# STLink_V3E_PWR.net
KiCad netlist of a schematic drawn in Altium Designer
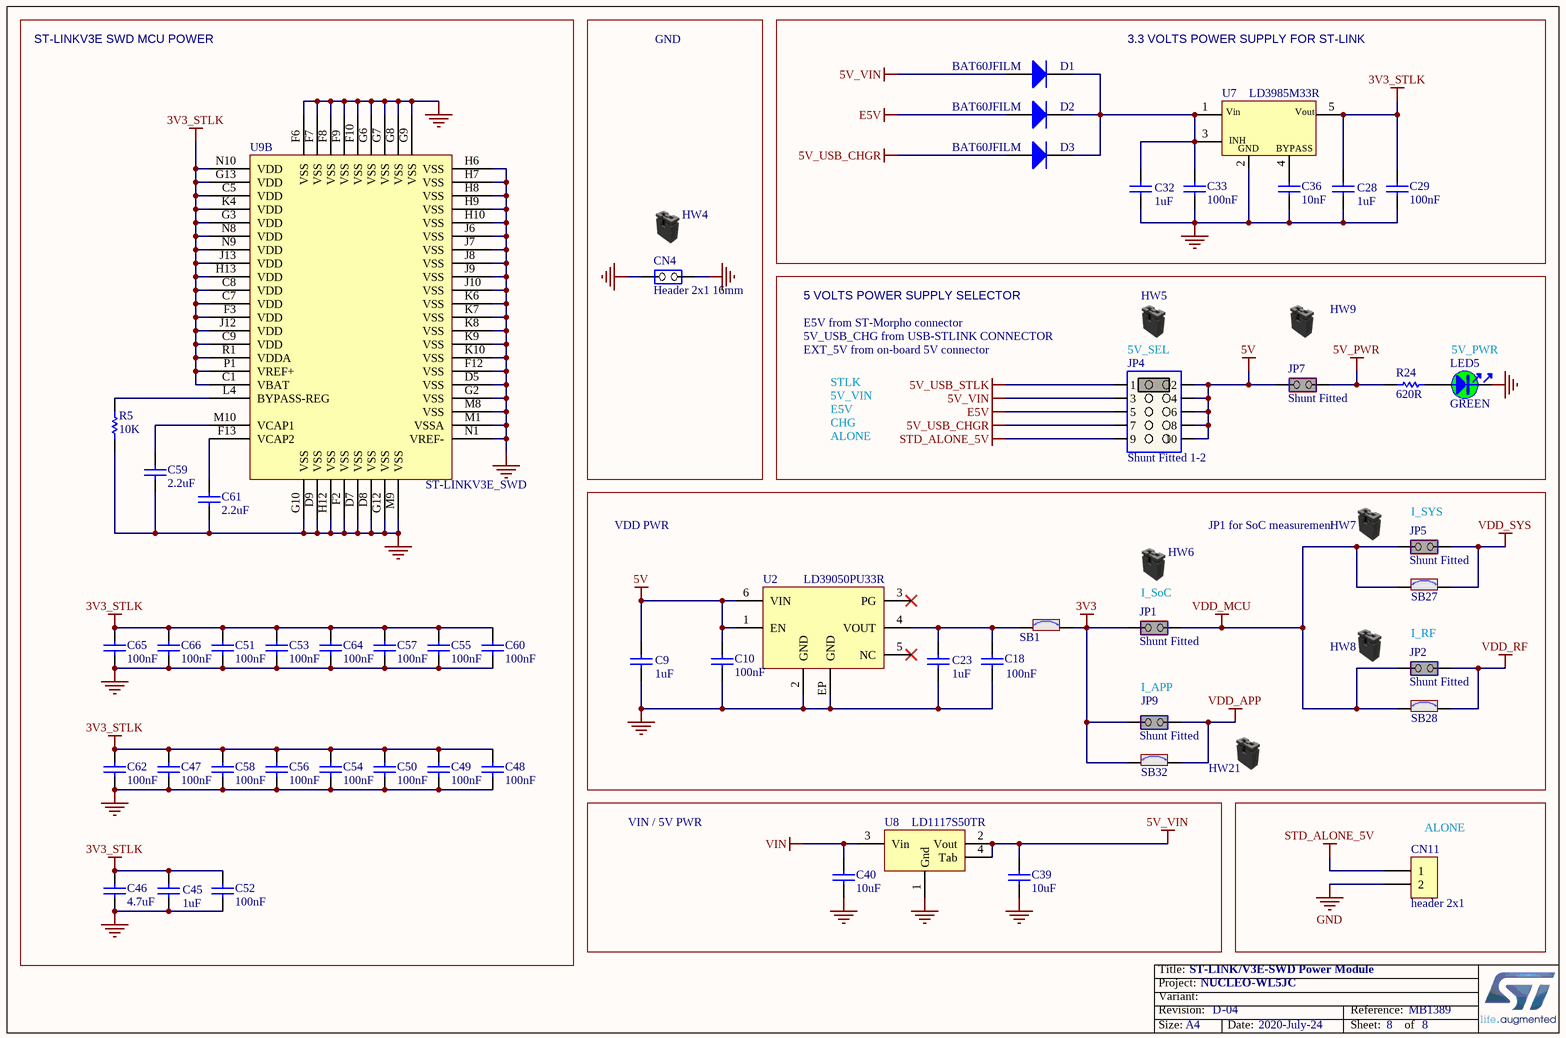
[diagram p0: STLink_V3E_PWR.SchDoc]

(export (version "E")
  (design (tool "Eeschema 10.0.6"))
  (components
    (comp (ref "C9")
      (value "1uF")
      (footprint "C0603")
      (description "Capacitor, MLCC, 1uF, 16V, X5R, 10%, 0603, T=0,8mm")
      (fields
        (field (name "INTERNAL_PART_NUMBER") "MCD-00010")
        (field (name "MANUFACTURER_PART_NUMBER") "CC0603KRX5R7BB105")
        (field (name "PROVIDED_BY") "SUBCO")
      )
      (libsource (lib "MCD_PARTS_database") (part "Capacitor"))
    )
    (comp (ref "C10")
      (value "100nF")
      (footprint "C0402")
      (description "Capacitor, MLCC, 100nF, 16V, X7R, 10%, 0402, T=0,5mm")
      (fields
        (field (name "INTERNAL_PART_NUMBER") "MCD-00102")
        (field (name "MANUFACTURER_PART_NUMBER") "CC0402KRX7R7BB104")
        (field (name "PROVIDED_BY") "SUBCO")
      )
      (libsource (lib "MCD_PARTS_database") (part "Capacitor"))
    )
    (comp (ref "C18")
      (value "100nF")
      (footprint "C0402")
      (description "Capacitor, MLCC, 100nF, 16V, X7R, 10%, 0402, T=0,5mm")
      (fields
        (field (name "INTERNAL_PART_NUMBER") "MCD-00102")
        (field (name "MANUFACTURER_PART_NUMBER") "CC0402KRX7R7BB104")
        (field (name "PROVIDED_BY") "SUBCO")
      )
      (libsource (lib "MCD_PARTS_database") (part "Capacitor"))
    )
    (comp (ref "C23")
      (value "1uF")
      (footprint "C0603")
      (description "Capacitor, MLCC, 1uF, 16V, X5R, 10%, 0603, T=0,8mm")
      (fields
        (field (name "INTERNAL_PART_NUMBER") "MCD-00010")
        (field (name "MANUFACTURER_PART_NUMBER") "CC0603KRX5R7BB105")
        (field (name "PROVIDED_BY") "SUBCO")
      )
      (libsource (lib "MCD_PARTS_database") (part "Capacitor"))
    )
    (comp (ref "C28")
      (value "1uF")
      (footprint "C0603")
      (description "Capacitor, MLCC, 1uF, 16V, X5R, 10%, 0603, T=0,8mm")
      (fields
        (field (name "INTERNAL_PART_NUMBER") "MCD-00010")
        (field (name "MANUFACTURER_PART_NUMBER") "CC0603KRX5R7BB105")
        (field (name "PROVIDED_BY") "SUBCO")
      )
      (libsource (lib "MCD_PARTS_database") (part "Capacitor"))
    )
    (comp (ref "C29")
      (value "100nF")
      (footprint "C0402")
      (description "Capacitor, MLCC, 100nF, 16V, X7R, 10%, 0402, T=0,5mm")
      (fields
        (field (name "INTERNAL_PART_NUMBER") "MCD-00102")
        (field (name "MANUFACTURER_PART_NUMBER") "CC0402KRX7R7BB104")
        (field (name "PROVIDED_BY") "SUBCO")
      )
      (libsource (lib "MCD_PARTS_database") (part "Capacitor"))
    )
    (comp (ref "C32")
      (value "1uF")
      (footprint "C0603")
      (description "Capacitor, MLCC, 1uF, 16V, X5R, 10%, 0603, T=0,8mm")
      (fields
        (field (name "INTERNAL_PART_NUMBER") "MCD-00010")
        (field (name "MANUFACTURER_PART_NUMBER") "CC0603KRX5R7BB105")
        (field (name "PROVIDED_BY") "SUBCO")
      )
      (libsource (lib "MCD_PARTS_database") (part "Capacitor"))
    )
    (comp (ref "C33")
      (value "100nF")
      (footprint "C0402")
      (description "Capacitor, MLCC, 100nF, 16V, X7R, 10%, 0402, T=0,5mm")
      (fields
        (field (name "INTERNAL_PART_NUMBER") "MCD-00102")
        (field (name "MANUFACTURER_PART_NUMBER") "CC0402KRX7R7BB104")
        (field (name "PROVIDED_BY") "SUBCO")
      )
      (libsource (lib "MCD_PARTS_database") (part "Capacitor"))
    )
    (comp (ref "C36")
      (value "10nF")
      (footprint "C0402")
      (description "Capacitor, MLCC, 10nF, 16V, X7R, 10%, 0402, T=0.5mm")
      (fields
        (field (name "INTERNAL_PART_NUMBER") "MCD-00011")
        (field (name "MANUFACTURER_PART_NUMBER") "CC0402KRX7R7BB103")
        (field (name "PROVIDED_BY") "SUBCO")
      )
      (libsource (lib "MCD_PARTS_database") (part "Capacitor"))
    )
    (comp (ref "C39")
      (value "10uF")
      (footprint "C0805")
      (description "Capacitor, MLCC, 10uF, 25V, X5R, 10%, 0805, T=0,85mm")
      (fields
        (field (name "INTERNAL_PART_NUMBER") "MCD-00014")
        (field (name "MANUFACTURER_PART_NUMBER") "CC0805KRX5R8BB106")
        (field (name "PROVIDED_BY") "SUBCO")
      )
      (libsource (lib "MCD_PARTS_database") (part "Capacitor"))
    )
    (comp (ref "C40")
      (value "10uF")
      (footprint "C0805")
      (description "Capacitor, MLCC, 10uF, 25V, X5R, 10%, 0805, T=0,85mm")
      (fields
        (field (name "INTERNAL_PART_NUMBER") "MCD-00014")
        (field (name "MANUFACTURER_PART_NUMBER") "CC0805KRX5R8BB106")
        (field (name "PROVIDED_BY") "SUBCO")
      )
      (libsource (lib "MCD_PARTS_database") (part "Capacitor"))
    )
    (comp (ref "C45")
      (value "1uF")
      (footprint "C0603")
      (description "Capacitor, MLCC, 1uF, 16V, X5R, 10%, 0603, T=0,8mm")
      (fields
        (field (name "INTERNAL_PART_NUMBER") "MCD-00010")
        (field (name "MANUFACTURER_PART_NUMBER") "CC0603KRX5R7BB105")
        (field (name "PROVIDED_BY") "SUBCO")
      )
      (libsource (lib "MCD_PARTS_database") (part "Capacitor"))
    )
    (comp (ref "C46")
      (value "4.7uF")
      (footprint "C0603")
      (description "Capacitor, MLCC, 4.7uF, 16V, X5R, 10%, 0603, T=0.8mm")
      (fields
        (field (name "INTERNAL_PART_NUMBER") "MCD-00009")
        (field (name "MANUFACTURER_PART_NUMBER") "CC0603KRX5R7BB475")
        (field (name "PROVIDED_BY") "SUBCO")
      )
      (libsource (lib "MCD_PARTS_database") (part "Capacitor"))
    )
    (comp (ref "C47")
      (value "100nF")
      (footprint "C0402")
      (description "Capacitor, MLCC, 100nF, 16V, X7R, 10%, 0402, T=0,5mm")
      (fields
        (field (name "INTERNAL_PART_NUMBER") "MCD-00102")
        (field (name "MANUFACTURER_PART_NUMBER") "CC0402KRX7R7BB104")
        (field (name "PROVIDED_BY") "SUBCO")
      )
      (libsource (lib "MCD_PARTS_database") (part "Capacitor"))
    )
    (comp (ref "C48")
      (value "100nF")
      (footprint "C0402")
      (description "Capacitor, MLCC, 100nF, 16V, X7R, 10%, 0402, T=0,5mm")
      (fields
        (field (name "INTERNAL_PART_NUMBER") "MCD-00102")
        (field (name "MANUFACTURER_PART_NUMBER") "CC0402KRX7R7BB104")
        (field (name "PROVIDED_BY") "SUBCO")
      )
      (libsource (lib "MCD_PARTS_database") (part "Capacitor"))
    )
    (comp (ref "C49")
      (value "100nF")
      (footprint "C0402")
      (description "Capacitor, MLCC, 100nF, 16V, X7R, 10%, 0402, T=0,5mm")
      (fields
        (field (name "INTERNAL_PART_NUMBER") "MCD-00102")
        (field (name "MANUFACTURER_PART_NUMBER") "CC0402KRX7R7BB104")
        (field (name "PROVIDED_BY") "SUBCO")
      )
      (libsource (lib "MCD_PARTS_database") (part "Capacitor"))
    )
    (comp (ref "C50")
      (value "100nF")
      (footprint "C0402")
      (description "Capacitor, MLCC, 100nF, 16V, X7R, 10%, 0402, T=0,5mm")
      (fields
        (field (name "INTERNAL_PART_NUMBER") "MCD-00102")
        (field (name "MANUFACTURER_PART_NUMBER") "CC0402KRX7R7BB104")
        (field (name "PROVIDED_BY") "SUBCO")
      )
      (libsource (lib "MCD_PARTS_database") (part "Capacitor"))
    )
    (comp (ref "C51")
      (value "100nF")
      (footprint "C0402")
      (description "Capacitor, MLCC, 100nF, 16V, X7R, 10%, 0402, T=0,5mm")
      (fields
        (field (name "INTERNAL_PART_NUMBER") "MCD-00102")
        (field (name "MANUFACTURER_PART_NUMBER") "CC0402KRX7R7BB104")
        (field (name "PROVIDED_BY") "SUBCO")
      )
      (libsource (lib "MCD_PARTS_database") (part "Capacitor"))
    )
    (comp (ref "C52")
      (value "100nF")
      (footprint "C0402")
      (description "Capacitor, MLCC, 100nF, 16V, X7R, 10%, 0402, T=0,5mm")
      (fields
        (field (name "INTERNAL_PART_NUMBER") "MCD-00102")
        (field (name "MANUFACTURER_PART_NUMBER") "CC0402KRX7R7BB104")
        (field (name "PROVIDED_BY") "SUBCO")
      )
      (libsource (lib "MCD_PARTS_database") (part "Capacitor"))
    )
    (comp (ref "C53")
      (value "100nF")
      (footprint "C0402")
      (description "Capacitor, MLCC, 100nF, 16V, X7R, 10%, 0402, T=0,5mm")
      (fields
        (field (name "INTERNAL_PART_NUMBER") "MCD-00102")
        (field (name "MANUFACTURER_PART_NUMBER") "CC0402KRX7R7BB104")
        (field (name "PROVIDED_BY") "SUBCO")
      )
      (libsource (lib "MCD_PARTS_database") (part "Capacitor"))
    )
    (comp (ref "C54")
      (value "100nF")
      (footprint "C0402")
      (description "Capacitor, MLCC, 100nF, 16V, X7R, 10%, 0402, T=0,5mm")
      (fields
        (field (name "INTERNAL_PART_NUMBER") "MCD-00102")
        (field (name "MANUFACTURER_PART_NUMBER") "CC0402KRX7R7BB104")
        (field (name "PROVIDED_BY") "SUBCO")
      )
      (libsource (lib "MCD_PARTS_database") (part "Capacitor"))
    )
    (comp (ref "C55")
      (value "100nF")
      (footprint "C0402")
      (description "Capacitor, MLCC, 100nF, 16V, X7R, 10%, 0402, T=0,5mm")
      (fields
        (field (name "INTERNAL_PART_NUMBER") "MCD-00102")
        (field (name "MANUFACTURER_PART_NUMBER") "CC0402KRX7R7BB104")
        (field (name "PROVIDED_BY") "SUBCO")
      )
      (libsource (lib "MCD_PARTS_database") (part "Capacitor"))
    )
    (comp (ref "C56")
      (value "100nF")
      (footprint "C0402")
      (description "Capacitor, MLCC, 100nF, 16V, X7R, 10%, 0402, T=0,5mm")
      (fields
        (field (name "INTERNAL_PART_NUMBER") "MCD-00102")
        (field (name "MANUFACTURER_PART_NUMBER") "CC0402KRX7R7BB104")
        (field (name "PROVIDED_BY") "SUBCO")
      )
      (libsource (lib "MCD_PARTS_database") (part "Capacitor"))
    )
    (comp (ref "C57")
      (value "100nF")
      (footprint "C0402")
      (description "Capacitor, MLCC, 100nF, 16V, X7R, 10%, 0402, T=0,5mm")
      (fields
        (field (name "INTERNAL_PART_NUMBER") "MCD-00102")
        (field (name "MANUFACTURER_PART_NUMBER") "CC0402KRX7R7BB104")
        (field (name "PROVIDED_BY") "SUBCO")
      )
      (libsource (lib "MCD_PARTS_database") (part "Capacitor"))
    )
    (comp (ref "C58")
      (value "100nF")
      (footprint "C0402")
      (description "Capacitor, MLCC, 100nF, 16V, X7R, 10%, 0402, T=0,5mm")
      (fields
        (field (name "INTERNAL_PART_NUMBER") "MCD-00102")
        (field (name "MANUFACTURER_PART_NUMBER") "CC0402KRX7R7BB104")
        (field (name "PROVIDED_BY") "SUBCO")
      )
      (libsource (lib "MCD_PARTS_database") (part "Capacitor"))
    )
    (comp (ref "C59")
      (value "2.2uF")
      (footprint "C0603")
      (description "Capacitor, MLCC, 2.2uF, 10V, X5R, 10%, 0603, T=0,8mm")
      (fields
        (field (name "INTERNAL_PART_NUMBER") "MCD-00012")
        (field (name "MANUFACTURER_PART_NUMBER") "CC0603KRX5R6BB225")
        (field (name "PROVIDED_BY") "SUBCO")
      )
      (libsource (lib "MCD_PARTS_database") (part "Capacitor"))
    )
    (comp (ref "C60")
      (value "100nF")
      (footprint "C0402")
      (description "Capacitor, MLCC, 100nF, 16V, X7R, 10%, 0402, T=0,5mm")
      (fields
        (field (name "INTERNAL_PART_NUMBER") "MCD-00102")
        (field (name "MANUFACTURER_PART_NUMBER") "CC0402KRX7R7BB104")
        (field (name "PROVIDED_BY") "SUBCO")
      )
      (libsource (lib "MCD_PARTS_database") (part "Capacitor"))
    )
    (comp (ref "C61")
      (value "2.2uF")
      (footprint "C0603")
      (description "Capacitor, MLCC, 2.2uF, 10V, X5R, 10%, 0603, T=0,8mm")
      (fields
        (field (name "INTERNAL_PART_NUMBER") "MCD-00012")
        (field (name "MANUFACTURER_PART_NUMBER") "CC0603KRX5R6BB225")
        (field (name "PROVIDED_BY") "SUBCO")
      )
      (libsource (lib "MCD_PARTS_database") (part "Capacitor"))
    )
    (comp (ref "C62")
      (value "100nF")
      (footprint "C0402")
      (description "Capacitor, MLCC, 100nF, 16V, X7R, 10%, 0402, T=0,5mm")
      (fields
        (field (name "INTERNAL_PART_NUMBER") "MCD-00102")
        (field (name "MANUFACTURER_PART_NUMBER") "CC0402KRX7R7BB104")
        (field (name "PROVIDED_BY") "SUBCO")
      )
      (libsource (lib "MCD_PARTS_database") (part "Capacitor"))
    )
    (comp (ref "C64")
      (value "100nF")
      (footprint "C0402")
      (description "Capacitor, MLCC, 100nF, 16V, X7R, 10%, 0402, T=0,5mm")
      (fields
        (field (name "INTERNAL_PART_NUMBER") "MCD-00102")
        (field (name "MANUFACTURER_PART_NUMBER") "CC0402KRX7R7BB104")
        (field (name "PROVIDED_BY") "SUBCO")
      )
      (libsource (lib "MCD_PARTS_database") (part "Capacitor"))
    )
    (comp (ref "C65")
      (value "100nF")
      (footprint "C0402")
      (description "Capacitor, MLCC, 100nF, 16V, X7R, 10%, 0402, T=0,5mm")
      (fields
        (field (name "INTERNAL_PART_NUMBER") "MCD-00102")
        (field (name "MANUFACTURER_PART_NUMBER") "CC0402KRX7R7BB104")
        (field (name "PROVIDED_BY") "SUBCO")
      )
      (libsource (lib "MCD_PARTS_database") (part "Capacitor"))
    )
    (comp (ref "C66")
      (value "100nF")
      (footprint "C0402")
      (description "Capacitor, MLCC, 100nF, 16V, X7R, 10%, 0402, T=0,5mm")
      (fields
        (field (name "INTERNAL_PART_NUMBER") "MCD-00102")
        (field (name "MANUFACTURER_PART_NUMBER") "CC0402KRX7R7BB104")
        (field (name "PROVIDED_BY") "SUBCO")
      )
      (libsource (lib "MCD_PARTS_database") (part "Capacitor"))
    )
    (comp (ref "CN4")
      (value "Header 2x1 16mm")
      (footprint "CON_SAMTEC_TSW-102-09-X-S")
      (description "Header, 2x1, 2,54mm, VR, TH, Height 5.84mm/10.16mm")
      (fields
        (field (name "INTERNAL_PART_NUMBER") "MCD-00214")
        (field (name "MANUFACTURER_PART_NUMBER") "TSW-102-09-x-S")
        (field (name "PROVIDED_BY") "SUBCO")
      )
      (libsource (lib "MCD_PARTS_database") (part "Jumper_Header 2x1"))
    )
    (comp (ref "CN11")
      (value "header 2x1")
      (footprint "CON_988-JIUBABA_PHFS25-11-02-G0B115-T-1")
      (description "Header, 2x1, 2.54mm, VR, TH, Height 6mm/3mm")
      (fields
        (field (name "INTERNAL_PART_NUMBER") "MCD-00314")
        (field (name "MANUFACTURER_PART_NUMBER") "PHFS25-11-02-G0B115-T-1")
        (field (name "PROVIDED_BY") "SUBCO")
      )
      (libsource (lib "MCD_PARTS_database") (part "Header 2x1"))
    )
    (comp (ref "D1")
      (value "BAT60JFILM")
      (footprint "DIO_SOD323")
      (fields
        (field (name "INTERNAL_PART_NUMBER") "MCD-00034")
        (field (name "MANUFACTURER") "STMICROELECTRONICS")
        (field (name "BMS_PART_NUMBER") "9151097")
        (field (name "PROVIDED_BY") "SUBCO with ST control")
      )
      (libsource (lib "MCD_PARTS_database") (part "BAT60JFILM"))
    )
    (comp (ref "D2")
      (value "BAT60JFILM")
      (footprint "DIO_SOD323")
      (fields
        (field (name "INTERNAL_PART_NUMBER") "MCD-00034")
        (field (name "MANUFACTURER") "STMICROELECTRONICS")
        (field (name "BMS_PART_NUMBER") "9151097")
        (field (name "PROVIDED_BY") "SUBCO with ST control")
      )
      (libsource (lib "MCD_PARTS_database") (part "BAT60JFILM"))
    )
    (comp (ref "D3")
      (value "BAT60JFILM")
      (footprint "DIO_SOD323")
      (fields
        (field (name "INTERNAL_PART_NUMBER") "MCD-00034")
        (field (name "MANUFACTURER") "STMICROELECTRONICS")
        (field (name "BMS_PART_NUMBER") "9151097")
        (field (name "PROVIDED_BY") "SUBCO with ST control")
      )
      (libsource (lib "MCD_PARTS_database") (part "BAT60JFILM"))
    )
    (comp (ref "HW4")
      (value "~")
      (description "SHUNT 2.54mm BLACK")
      (fields
        (field (name "INTERNAL_PART_NUMBER") "MCD-00043")
        (field (name "MANUFACTURER_PART_NUMBER") "SNT-100-BK-G")
        (field (name "PROVIDED_BY") "SUBCO")
      )
      (libsource (lib "MCD_PARTS_database") (part "Shunt Black 2.54mm"))
    )
    (comp (ref "HW5")
      (value "~")
      (description "SHUNT 2.54mm BLACK")
      (fields
        (field (name "INTERNAL_PART_NUMBER") "MCD-00043")
        (field (name "MANUFACTURER_PART_NUMBER") "SNT-100-BK-G")
        (field (name "PROVIDED_BY") "SUBCO")
      )
      (libsource (lib "MCD_PARTS_database") (part "Shunt Black 2.54mm"))
    )
    (comp (ref "HW6")
      (value "~")
      (description "SHUNT 2.54mm BLACK")
      (fields
        (field (name "INTERNAL_PART_NUMBER") "MCD-00043")
        (field (name "MANUFACTURER_PART_NUMBER") "SNT-100-BK-G")
        (field (name "PROVIDED_BY") "SUBCO")
      )
      (libsource (lib "MCD_PARTS_database") (part "Shunt Black 2.54mm"))
    )
    (comp (ref "HW7")
      (value "~")
      (description "SHUNT 2.54mm BLACK")
      (fields
        (field (name "INTERNAL_PART_NUMBER") "MCD-00043")
        (field (name "MANUFACTURER_PART_NUMBER") "SNT-100-BK-G")
        (field (name "PROVIDED_BY") "SUBCO")
      )
      (libsource (lib "MCD_PARTS_database") (part "Shunt Black 2.54mm"))
    )
    (comp (ref "HW8")
      (value "~")
      (description "SHUNT 2.54mm BLACK")
      (fields
        (field (name "INTERNAL_PART_NUMBER") "MCD-00043")
        (field (name "MANUFACTURER_PART_NUMBER") "SNT-100-BK-G")
        (field (name "PROVIDED_BY") "SUBCO")
      )
      (libsource (lib "MCD_PARTS_database") (part "Shunt Black 2.54mm"))
    )
    (comp (ref "HW9")
      (value "~")
      (description "SHUNT 2.54mm BLACK")
      (fields
        (field (name "INTERNAL_PART_NUMBER") "MCD-00043")
        (field (name "MANUFACTURER_PART_NUMBER") "SNT-100-BK-G")
        (field (name "PROVIDED_BY") "SUBCO")
      )
      (libsource (lib "MCD_PARTS_database") (part "Shunt Black 2.54mm"))
    )
    (comp (ref "HW21")
      (value "~")
      (description "SHUNT 2.54mm BLACK")
      (fields
        (field (name "INTERNAL_PART_NUMBER") "MCD-00043")
        (field (name "MANUFACTURER_PART_NUMBER") "SNT-100-BK-G")
        (field (name "PROVIDED_BY") "SUBCO")
      )
      (libsource (lib "MCD_PARTS_database") (part "Shunt Black 2.54mm"))
    )
    (comp (ref "JP1")
      (value "Shunt Fitted")
      (footprint "CON_SAMTEC_TSW-102-07-G-S")
      (description "Header, 2x1, 2,54mm, VR, TH, Height 5.84mm/2.54mm - Shunt Fitted by default")
      (fields
        (field (name "INTERNAL_PART_NUMBER") "MCD-00683")
        (field (name "MANUFACTURER_PART_NUMBER") "TSW-102-07-x-S")
        (field (name "PROVIDED_BY") "SUBCO")
      )
      (libsource (lib "MCD_PARTS_database") (part "Jumper_Header 2x1 Fitted"))
    )
    (comp (ref "JP2")
      (value "Shunt Fitted")
      (footprint "CON_SAMTEC_TSW-102-07-G-S")
      (description "Header, 2x1, 2,54mm, VR, TH, Height 5.84mm/2.54mm - Shunt Fitted by default")
      (fields
        (field (name "INTERNAL_PART_NUMBER") "MCD-00683")
        (field (name "MANUFACTURER_PART_NUMBER") "TSW-102-07-x-S")
        (field (name "PROVIDED_BY") "SUBCO")
      )
      (libsource (lib "MCD_PARTS_database") (part "Jumper_Header 2x1 Fitted"))
    )
    (comp (ref "JP4")
      (value "Shunt Fitted 1-2")
      (footprint "CON_SAMTEC_TSW-105-07-X-D")
      (description "Header, 5x2, 2,54mm, VR, TH, Height 5.84mm/2.54mm - Shunt Fitted 1-2")
      (fields
        (field (name "INTERNAL_PART_NUMBER") "MCD-01203")
        (field (name "MANUFACTURER_PART_NUMBER") "TSW-105-07-x-D")
        (field (name "PROVIDED_BY") "SUBCO")
      )
      (libsource (lib "MCD_PARTS_database") (part "Jumper_Header 5x2 Fitted 1-2"))
    )
    (comp (ref "JP5")
      (value "Shunt Fitted")
      (footprint "CON_SAMTEC_TSW-102-07-G-S")
      (description "Header, 2x1, 2,54mm, VR, TH, Height 5.84mm/2.54mm - Shunt Fitted by default")
      (fields
        (field (name "INTERNAL_PART_NUMBER") "MCD-00683")
        (field (name "MANUFACTURER_PART_NUMBER") "TSW-102-07-x-S")
        (field (name "PROVIDED_BY") "SUBCO")
      )
      (libsource (lib "MCD_PARTS_database") (part "Jumper_Header 2x1 Fitted"))
    )
    (comp (ref "JP7")
      (value "Shunt Fitted")
      (footprint "CON_SAMTEC_TSW-102-07-G-S")
      (description "Header, 2x1, 2,54mm, VR, TH, Height 5.84mm/2.54mm - Shunt Fitted by default")
      (fields
        (field (name "INTERNAL_PART_NUMBER") "MCD-00683")
        (field (name "MANUFACTURER_PART_NUMBER") "TSW-102-07-x-S")
        (field (name "PROVIDED_BY") "SUBCO")
      )
      (libsource (lib "MCD_PARTS_database") (part "Jumper_Header 2x1 Fitted"))
    )
    (comp (ref "JP9")
      (value "Shunt Fitted")
      (footprint "CON_SAMTEC_TSW-102-07-G-S")
      (description "Header, 2x1, 2,54mm, VR, TH, Height 5.84mm/2.54mm - Shunt Fitted by default")
      (fields
        (field (name "INTERNAL_PART_NUMBER") "MCD-00683")
        (field (name "MANUFACTURER_PART_NUMBER") "TSW-102-07-x-S")
        (field (name "PROVIDED_BY") "SUBCO")
      )
      (libsource (lib "MCD_PARTS_database") (part "Jumper_Header 2x1 Fitted"))
    )
    (comp (ref "LED5")
      (value "GREEN")
      (footprint "LED_0603_OSRAM_LG-Q396-PS-35_GREEN_1A2K_H0P4")
      (description "LED Green, 0603 SMD, Forward Voltage Typ=2V, Max=2.5V")
      (fields
        (field (name "INTERNAL_PART_NUMBER") "MCD-00588")
        (field (name "MANUFACTURER_PART_NUMBER") "LG Q396-PS-35")
        (field (name "PROVIDED_BY") "SUBCO")
      )
      (libsource (lib "MCD_PARTS_database") (part "LED_green"))
    )
    (comp (ref "R5")
      (value "10K")
      (footprint "R0402")
      (description "Resistor,10K,0402,1%,1/16W")
      (fields
        (field (name "INTERNAL_PART_NUMBER") "MCD-00053")
        (field (name "MANUFACTURER_PART_NUMBER") "RC0402FR-0710KL")
        (field (name "PROVIDED_BY") "SUBCO")
      )
      (libsource (lib "MCD_PARTS_database") (part "Resistor"))
    )
    (comp (ref "R24")
      (value "620R")
      (footprint "R0402")
      (description "Resistor,620R,0402,1%,1/16W")
      (fields
        (field (name "INTERNAL_PART_NUMBER") "MCD-00499")
        (field (name "MANUFACTURER_PART_NUMBER") "RC0402FR-07620RL")
        (field (name "PROVIDED_BY") "SUBCO")
      )
      (libsource (lib "MCD_PARTS_database") (part "Resistor"))
    )
    (comp (ref "SB1")
      (value "~")
      (footprint "SOLDER-BRIDGE_R0603-0R")
      (description "Solder Bridge ON")
      (fields
        (field (name "INTERNAL_PART_NUMBER") "MCD-00071")
        (field (name "MANUFACTURER_PART_NUMBER") "RC0603JR-070RL")
        (field (name "PROVIDED_BY") "SUBCO")
      )
      (libsource (lib "MCD_PARTS_database") (part "SB_ON"))
    )
    (comp (ref "SB27")
      (value "~")
      (footprint "SOLDER-BRIDGE_R0603-0R")
      (description "Solder Bridge ON")
      (fields
        (field (name "INTERNAL_PART_NUMBER") "MCD-00071")
        (field (name "MANUFACTURER_PART_NUMBER") "RC0603JR-070RL")
        (field (name "PROVIDED_BY") "SUBCO")
      )
      (libsource (lib "MCD_PARTS_database") (part "SB_ON"))
    )
    (comp (ref "SB28")
      (value "~")
      (footprint "SOLDER-BRIDGE_R0603-0R")
      (description "Solder Bridge ON")
      (fields
        (field (name "INTERNAL_PART_NUMBER") "MCD-00071")
        (field (name "MANUFACTURER_PART_NUMBER") "RC0603JR-070RL")
        (field (name "PROVIDED_BY") "SUBCO")
      )
      (libsource (lib "MCD_PARTS_database") (part "SB_ON"))
    )
    (comp (ref "SB32")
      (value "~")
      (footprint "SOLDER-BRIDGE_R0603-0R")
      (description "Solder Bridge ON")
      (fields
        (field (name "INTERNAL_PART_NUMBER") "MCD-00071")
        (field (name "MANUFACTURER_PART_NUMBER") "RC0603JR-070RL")
        (field (name "PROVIDED_BY") "SUBCO")
      )
      (libsource (lib "MCD_PARTS_database") (part "SB_ON"))
    )
    (comp (ref "U2")
      (value "LD39050PU33R")
      (footprint "ICC_DFN6-EPAD_3X3_P095")
      (description "Low quiescent current and low noise voltage regulators")
      (fields
        (field (name "INTERNAL_PART_NUMBER") "MCD-00215")
        (field (name "MANUFACTURER") "STMICROELECTRONICS")
        (field (name "PROVIDED_BY") "SUBCO with ST control")
      )
      (libsource (lib "MCD_PARTS_database") (part "LD39050PU33R"))
    )
    (comp (ref "U7")
      (value "LD3985M33R")
      (footprint "REG_SOT23-5L")
      (description "Ultra low drop-low noise BiCMOS voltage, regulators low ESR capacitors compatible")
      (fields
        (field (name "INTERNAL_PART_NUMBER") "MCD-00086")
        (field (name "MANUFACTURER") "STMICROELECTRONICS")
        (field (name "PROVIDED_BY") "SUBCO with ST control")
      )
      (libsource (lib "MCD_PARTS_database") (part "LD3985M33R"))
    )
    (comp (ref "U8")
      (value "LD1117S50TR")
      (footprint "REG_SOT223-TAB")
      (description "IC REG LDO 5V 0.8A SOT223")
      (fields
        (field (name "INTERNAL_PART_NUMBER") "MCD-00088")
        (field (name "MANUFACTURER") "STMICROELECTRONICS")
        (field (name "PROVIDED_BY") "SUBCO with ST control")
      )
      (libsource (lib "MCD_PARTS_database") (part "LD1117S50TR"))
    )
    (comp (ref "U9")
      (value "ST-LINKV3E_SWD")
      (footprint "ICC_UFBGA201_176+25_10X10_P065")
      (description "STM32F723IEK  (STM32F7) BGA176")
      (fields
        (field (name "INTERNAL_PART_NUMBER") "MCD-00596")
        (field (name "MANUFACTURER_PART_NUMBER") "STM32F723IEK6")
        (field (name "PROVIDED_BY") "SUBCO with ST control")
      )
      (libsource (lib "MCD_PARTS_database") (part "ST-LINKV3E_SWD"))
    )
  )
  (nets
    (net (code "1") (name "3V3") (class "Default")
      (node (ref "JP1") (pin "1") (pinfunction "COMMON_1") (pintype "passive"))
      (node (ref "JP9") (pin "1") (pinfunction "COMMON_1") (pintype "passive"))
      (node (ref "SB1") (pin "2") (pinfunction "2_2") (pintype "passive"))
      (node (ref "SB32") (pin "1") (pinfunction "1_1") (pintype "passive"))
    )
    (net (code "2") (name "3V3_STLK") (class "Default")
      (node (ref "C28") (pin "2") (pinfunction "2_2") (pintype "passive"))
      (node (ref "C29") (pin "2") (pinfunction "2_2") (pintype "passive"))
      (node (ref "C45") (pin "2") (pinfunction "2_2") (pintype "passive"))
      (node (ref "C46") (pin "2") (pinfunction "2_2") (pintype "passive"))
      (node (ref "C47") (pin "2") (pinfunction "2_2") (pintype "passive"))
      (node (ref "C48") (pin "2") (pinfunction "2_2") (pintype "passive"))
      (node (ref "C49") (pin "2") (pinfunction "2_2") (pintype "passive"))
      (node (ref "C50") (pin "2") (pinfunction "2_2") (pintype "passive"))
      (node (ref "C51") (pin "2") (pinfunction "2_2") (pintype "passive"))
      (node (ref "C52") (pin "2") (pinfunction "2_2") (pintype "passive"))
      (node (ref "C53") (pin "2") (pinfunction "2_2") (pintype "passive"))
      (node (ref "C54") (pin "2") (pinfunction "2_2") (pintype "passive"))
      (node (ref "C55") (pin "2") (pinfunction "2_2") (pintype "passive"))
      (node (ref "C56") (pin "2") (pinfunction "2_2") (pintype "passive"))
      (node (ref "C57") (pin "2") (pinfunction "2_2") (pintype "passive"))
      (node (ref "C58") (pin "2") (pinfunction "2_2") (pintype "passive"))
      (node (ref "C60") (pin "2") (pinfunction "2_2") (pintype "passive"))
      (node (ref "C62") (pin "2") (pinfunction "2_2") (pintype "passive"))
      (node (ref "C64") (pin "2") (pinfunction "2_2") (pintype "passive"))
      (node (ref "C65") (pin "2") (pinfunction "2_2") (pintype "passive"))
      (node (ref "C66") (pin "2") (pinfunction "2_2") (pintype "passive"))
      (node (ref "U7") (pin "5") (pinfunction "Vout_5") (pintype "passive"))
      (node (ref "U9") (pin "C1") (pinfunction "VBAT_C1") (pintype "passive"))
      (node (ref "U9") (pin "C5") (pinfunction "VDD_C5") (pintype "passive"))
      (node (ref "U9") (pin "C7") (pinfunction "VDD_C7") (pintype "passive"))
      (node (ref "U9") (pin "C8") (pinfunction "VDD_C8") (pintype "passive"))
      (node (ref "U9") (pin "C9") (pinfunction "VDD_C9") (pintype "passive"))
      (node (ref "U9") (pin "F3") (pinfunction "VDD_F3") (pintype "passive"))
      (node (ref "U9") (pin "G13") (pinfunction "VDD_G13") (pintype "passive"))
      (node (ref "U9") (pin "G3") (pinfunction "VDD_G3") (pintype "passive"))
      (node (ref "U9") (pin "H13") (pinfunction "VDD_H13") (pintype "passive"))
      (node (ref "U9") (pin "J12") (pinfunction "VDD_J12") (pintype "passive"))
      (node (ref "U9") (pin "J13") (pinfunction "VDD_J13") (pintype "passive"))
      (node (ref "U9") (pin "K4") (pinfunction "VDD_K4") (pintype "passive"))
      (node (ref "U9") (pin "N10") (pinfunction "VDD_N10") (pintype "passive"))
      (node (ref "U9") (pin "N8") (pinfunction "VDD_N8") (pintype "passive"))
      (node (ref "U9") (pin "N9") (pinfunction "VDD_N9") (pintype "passive"))
      (node (ref "U9") (pin "P1") (pinfunction "VREF+_P1") (pintype "passive"))
      (node (ref "U9") (pin "R1") (pinfunction "VDDA_R1") (pintype "passive"))
    )
    (net (code "3") (name "5V") (class "Default")
      (node (ref "C10") (pin "2") (pinfunction "2_2") (pintype "passive"))
      (node (ref "C9") (pin "2") (pinfunction "2_2") (pintype "passive"))
      (node (ref "JP4") (pin "10") (pinfunction "10_10") (pintype "passive"))
      (node (ref "JP4") (pin "2") (pinfunction "2_2") (pintype "passive"))
      (node (ref "JP4") (pin "4") (pinfunction "4_4") (pintype "passive"))
      (node (ref "JP4") (pin "6") (pinfunction "6_6") (pintype "passive"))
      (node (ref "JP4") (pin "8") (pinfunction "8_8") (pintype "passive"))
      (node (ref "JP7") (pin "1") (pinfunction "COMMON_1") (pintype "passive"))
      (node (ref "U2") (pin "1") (pinfunction "EN_1") (pintype "passive"))
      (node (ref "U2") (pin "6") (pinfunction "VIN_6") (pintype "passive"))
    )
    (net (code "4") (name "5V_PWR") (class "Default")
      (node (ref "JP7") (pin "2") (pinfunction "NO_2") (pintype "passive"))
      (node (ref "R24") (pin "1") (pinfunction "1_1") (pintype "passive"))
    )
    (net (code "5") (name "5V_USB_CHGR") (class "Default")
      (node (ref "D3") (pin "1") (pinfunction "A_1") (pintype "passive"))
      (node (ref "JP4") (pin "7") (pinfunction "7_7") (pintype "passive"))
    )
    (net (code "6") (name "5V_USB_STLK") (class "Default")
      (node (ref "JP4") (pin "1") (pinfunction "1_1") (pintype "passive"))
    )
    (net (code "7") (name "5V_VIN") (class "Default")
      (node (ref "C39") (pin "2") (pinfunction "2_2") (pintype "passive"))
      (node (ref "D1") (pin "1") (pinfunction "A_1") (pintype "passive"))
      (node (ref "JP4") (pin "3") (pinfunction "3_3") (pintype "passive"))
      (node (ref "U8") (pin "2") (pinfunction "Vout_2") (pintype "passive"))
      (node (ref "U8") (pin "4") (pinfunction "Tab_4") (pintype "passive"))
    )
    (net (code "8") (name "E5V") (class "Default")
      (node (ref "D2") (pin "1") (pinfunction "A_1") (pintype "passive"))
      (node (ref "JP4") (pin "5") (pinfunction "5_5") (pintype "passive"))
    )
    (net (code "9") (name "GND") (class "Default")
      (node (ref "C10") (pin "1") (pinfunction "1_1") (pintype "passive"))
      (node (ref "C18") (pin "1") (pinfunction "1_1") (pintype "passive"))
      (node (ref "C23") (pin "1") (pinfunction "1_1") (pintype "passive"))
      (node (ref "C28") (pin "1") (pinfunction "1_1") (pintype "passive"))
      (node (ref "C29") (pin "1") (pinfunction "1_1") (pintype "passive"))
      (node (ref "C32") (pin "1") (pinfunction "1_1") (pintype "passive"))
      (node (ref "C33") (pin "1") (pinfunction "1_1") (pintype "passive"))
      (node (ref "C36") (pin "1") (pinfunction "1_1") (pintype "passive"))
      (node (ref "C39") (pin "1") (pinfunction "1_1") (pintype "passive"))
      (node (ref "C40") (pin "1") (pinfunction "1_1") (pintype "passive"))
      (node (ref "C45") (pin "1") (pinfunction "1_1") (pintype "passive"))
      (node (ref "C46") (pin "1") (pinfunction "1_1") (pintype "passive"))
      (node (ref "C47") (pin "1") (pinfunction "1_1") (pintype "passive"))
      (node (ref "C48") (pin "1") (pinfunction "1_1") (pintype "passive"))
      (node (ref "C49") (pin "1") (pinfunction "1_1") (pintype "passive"))
      (node (ref "C50") (pin "1") (pinfunction "1_1") (pintype "passive"))
      (node (ref "C51") (pin "1") (pinfunction "1_1") (pintype "passive"))
      (node (ref "C52") (pin "1") (pinfunction "1_1") (pintype "passive"))
      (node (ref "C53") (pin "1") (pinfunction "1_1") (pintype "passive"))
      (node (ref "C54") (pin "1") (pinfunction "1_1") (pintype "passive"))
      (node (ref "C55") (pin "1") (pinfunction "1_1") (pintype "passive"))
      (node (ref "C56") (pin "1") (pinfunction "1_1") (pintype "passive"))
      (node (ref "C57") (pin "1") (pinfunction "1_1") (pintype "passive"))
      (node (ref "C58") (pin "1") (pinfunction "1_1") (pintype "passive"))
      (node (ref "C59") (pin "1") (pinfunction "1_1") (pintype "passive"))
      (node (ref "C60") (pin "1") (pinfunction "1_1") (pintype "passive"))
      (node (ref "C61") (pin "1") (pinfunction "1_1") (pintype "passive"))
      (node (ref "C62") (pin "1") (pinfunction "1_1") (pintype "passive"))
      (node (ref "C64") (pin "1") (pinfunction "1_1") (pintype "passive"))
      (node (ref "C65") (pin "1") (pinfunction "1_1") (pintype "passive"))
      (node (ref "C66") (pin "1") (pinfunction "1_1") (pintype "passive"))
      (node (ref "C9") (pin "1") (pinfunction "1_1") (pintype "passive"))
      (node (ref "CN11") (pin "2") (pinfunction "2_2") (pintype "passive"))
      (node (ref "CN4") (pin "1") (pinfunction "COMMON_1") (pintype "passive"))
      (node (ref "CN4") (pin "2") (pinfunction "NO_2") (pintype "passive"))
      (node (ref "LED5") (pin "2") (pintype "passive"))
      (node (ref "R5") (pin "1") (pinfunction "1_1") (pintype "passive"))
      (node (ref "U2") (pin "2") (pinfunction "GND_2") (pintype "passive"))
      (node (ref "U2") (pin "EP") (pinfunction "GND_EP") (pintype "passive"))
      (node (ref "U7") (pin "2") (pinfunction "GND_2") (pintype "passive"))
      (node (ref "U8") (pin "1") (pinfunction "Gnd_1") (pintype "passive"))
      (node (ref "U9") (pin "D5") (pinfunction "VSS_D5") (pintype "passive"))
      (node (ref "U9") (pin "D7") (pinfunction "VSS_D7") (pintype "passive"))
      (node (ref "U9") (pin "D8") (pinfunction "VSS_D8") (pintype "passive"))
      (node (ref "U9") (pin "D9") (pinfunction "VSS_D9") (pintype "passive"))
      (node (ref "U9") (pin "F10") (pinfunction "VSS_F10") (pintype "passive"))
      (node (ref "U9") (pin "F12") (pinfunction "VSS_F12") (pintype "passive"))
      (node (ref "U9") (pin "F2") (pinfunction "VSS_F2") (pintype "passive"))
      (node (ref "U9") (pin "F6") (pinfunction "VSS_F6") (pintype "passive"))
      (node (ref "U9") (pin "F7") (pinfunction "VSS_F7") (pintype "passive"))
      (node (ref "U9") (pin "F8") (pinfunction "VSS_F8") (pintype "passive"))
      (node (ref "U9") (pin "F9") (pinfunction "VSS_F9") (pintype "passive"))
      (node (ref "U9") (pin "G10") (pinfunction "VSS_G10") (pintype "passive"))
      (node (ref "U9") (pin "G12") (pinfunction "VSS_G12") (pintype "passive"))
      (node (ref "U9") (pin "G2") (pinfunction "VSS_G2") (pintype "passive"))
      (node (ref "U9") (pin "G6") (pinfunction "VSS_G6") (pintype "passive"))
      (node (ref "U9") (pin "G7") (pinfunction "VSS_G7") (pintype "passive"))
      (node (ref "U9") (pin "G8") (pinfunction "VSS_G8") (pintype "passive"))
      (node (ref "U9") (pin "G9") (pinfunction "VSS_G9") (pintype "passive"))
      (node (ref "U9") (pin "H10") (pinfunction "VSS_H10") (pintype "passive"))
      (node (ref "U9") (pin "H12") (pinfunction "VSS_H12") (pintype "passive"))
      (node (ref "U9") (pin "H6") (pinfunction "VSS_H6") (pintype "passive"))
      (node (ref "U9") (pin "H7") (pinfunction "VSS_H7") (pintype "passive"))
      (node (ref "U9") (pin "H8") (pinfunction "VSS_H8") (pintype "passive"))
      (node (ref "U9") (pin "H9") (pinfunction "VSS_H9") (pintype "passive"))
      (node (ref "U9") (pin "J10") (pinfunction "VSS_J10") (pintype "passive"))
      (node (ref "U9") (pin "J6") (pinfunction "VSS_J6") (pintype "passive"))
      (node (ref "U9") (pin "J7") (pinfunction "VSS_J7") (pintype "passive"))
      (node (ref "U9") (pin "J8") (pinfunction "VSS_J8") (pintype "passive"))
      (node (ref "U9") (pin "J9") (pinfunction "VSS_J9") (pintype "passive"))
      (node (ref "U9") (pin "K10") (pinfunction "VSS_K10") (pintype "passive"))
      (node (ref "U9") (pin "K6") (pinfunction "VSS_K6") (pintype "passive"))
      (node (ref "U9") (pin "K7") (pinfunction "VSS_K7") (pintype "passive"))
      (node (ref "U9") (pin "K8") (pinfunction "VSS_K8") (pintype "passive"))
      (node (ref "U9") (pin "K9") (pinfunction "VSS_K9") (pintype "passive"))
      (node (ref "U9") (pin "M1") (pinfunction "VSSA_M1") (pintype "passive"))
      (node (ref "U9") (pin "M8") (pinfunction "VSS_M8") (pintype "passive"))
      (node (ref "U9") (pin "M9") (pinfunction "VSS_M9") (pintype "passive"))
      (node (ref "U9") (pin "N1") (pinfunction "VREF-_N1") (pintype "passive"))
    )
    (net (code "10") (name "Net-(D1-K)") (class "Default")
      (node (ref "C32") (pin "2") (pinfunction "2_2") (pintype "passive"))
      (node (ref "C33") (pin "2") (pinfunction "2_2") (pintype "passive"))
      (node (ref "D1") (pin "2") (pinfunction "K_2") (pintype "passive"))
      (node (ref "D2") (pin "2") (pinfunction "K_2") (pintype "passive"))
      (node (ref "D3") (pin "2") (pinfunction "K_2") (pintype "passive"))
      (node (ref "U7") (pin "1") (pinfunction "Vin_1") (pintype "passive"))
      (node (ref "U7") (pin "3") (pinfunction "CE_3") (pintype "passive"))
    )
    (net (code "11") (name "Net-(LED5-Pad1)") (class "Default")
      (node (ref "LED5") (pin "1") (pintype "passive"))
      (node (ref "R24") (pin "2") (pinfunction "2_2") (pintype "passive"))
    )
    (net (code "12") (name "Net-(U2-VOUT)") (class "Default")
      (node (ref "C18") (pin "2") (pinfunction "2_2") (pintype "passive"))
      (node (ref "C23") (pin "2") (pinfunction "2_2") (pintype "passive"))
      (node (ref "SB1") (pin "1") (pinfunction "1_1") (pintype "passive"))
      (node (ref "U2") (pin "4") (pinfunction "VOUT_4") (pintype "passive"))
    )
    (net (code "13") (name "Net-(U7-BYPASS)") (class "Default")
      (node (ref "C36") (pin "2") (pinfunction "2_2") (pintype "passive"))
      (node (ref "U7") (pin "4") (pinfunction "BYPASS_4") (pintype "passive"))
    )
    (net (code "14") (name "Net-(U9B-BYPASS-REG)") (class "Default")
      (node (ref "R5") (pin "2") (pinfunction "2_2") (pintype "passive"))
      (node (ref "U9") (pin "L4") (pinfunction "BYPASS-REG_L4") (pintype "passive"))
    )
    (net (code "15") (name "Net-(U9B-VCAP1)") (class "Default")
      (node (ref "C59") (pin "2") (pinfunction "2_2") (pintype "passive"))
      (node (ref "U9") (pin "M10") (pinfunction "VCAP1_M10") (pintype "passive"))
    )
    (net (code "16") (name "Net-(U9B-VCAP2)") (class "Default")
      (node (ref "C61") (pin "2") (pinfunction "2_2") (pintype "passive"))
      (node (ref "U9") (pin "F13") (pinfunction "VCAP2_F13") (pintype "passive"))
    )
    (net (code "17") (name "STD_ALONE_5V") (class "Default")
      (node (ref "CN11") (pin "1") (pinfunction "1_1") (pintype "passive"))
      (node (ref "JP4") (pin "9") (pinfunction "9_9") (pintype "passive"))
    )
    (net (code "18") (name "VDD_APP") (class "Default")
      (node (ref "JP9") (pin "2") (pinfunction "NO_2") (pintype "passive"))
      (node (ref "SB32") (pin "2") (pinfunction "2_2") (pintype "passive"))
    )
    (net (code "19") (name "VDD_MCU") (class "Default")
      (node (ref "JP1") (pin "2") (pinfunction "NO_2") (pintype "passive"))
      (node (ref "JP2") (pin "1") (pinfunction "COMMON_1") (pintype "passive"))
      (node (ref "JP5") (pin "1") (pinfunction "COMMON_1") (pintype "passive"))
      (node (ref "SB27") (pin "1") (pinfunction "1_1") (pintype "passive"))
      (node (ref "SB28") (pin "1") (pinfunction "1_1") (pintype "passive"))
    )
    (net (code "20") (name "VDD_RF") (class "Default")
      (node (ref "JP2") (pin "2") (pinfunction "NO_2") (pintype "passive"))
      (node (ref "SB28") (pin "2") (pinfunction "2_2") (pintype "passive"))
    )
    (net (code "21") (name "VDD_SYS") (class "Default")
      (node (ref "JP5") (pin "2") (pinfunction "NO_2") (pintype "passive"))
      (node (ref "SB27") (pin "2") (pinfunction "2_2") (pintype "passive"))
    )
    (net (code "22") (name "VIN") (class "Default")
      (node (ref "C40") (pin "2") (pinfunction "2_2") (pintype "passive"))
      (node (ref "U8") (pin "3") (pinfunction "Vin_3") (pintype "passive"))
    )
    (net (code "23") (name "unconnected-(U2-NC-Pad5)") (class "Default")
      (node (ref "U2") (pin "5") (pinfunction "NC_5") (pintype "passive+no_connect"))
    )
    (net (code "24") (name "unconnected-(U2-PG-Pad3)") (class "Default")
      (node (ref "U2") (pin "3") (pinfunction "PG_3") (pintype "passive+no_connect"))
    )
  )
)
